# KC_BaseBoard4CompareTest-V0_1_NT_MIRR.net
KiCad netlist of a schematic drawn in Altium Designer
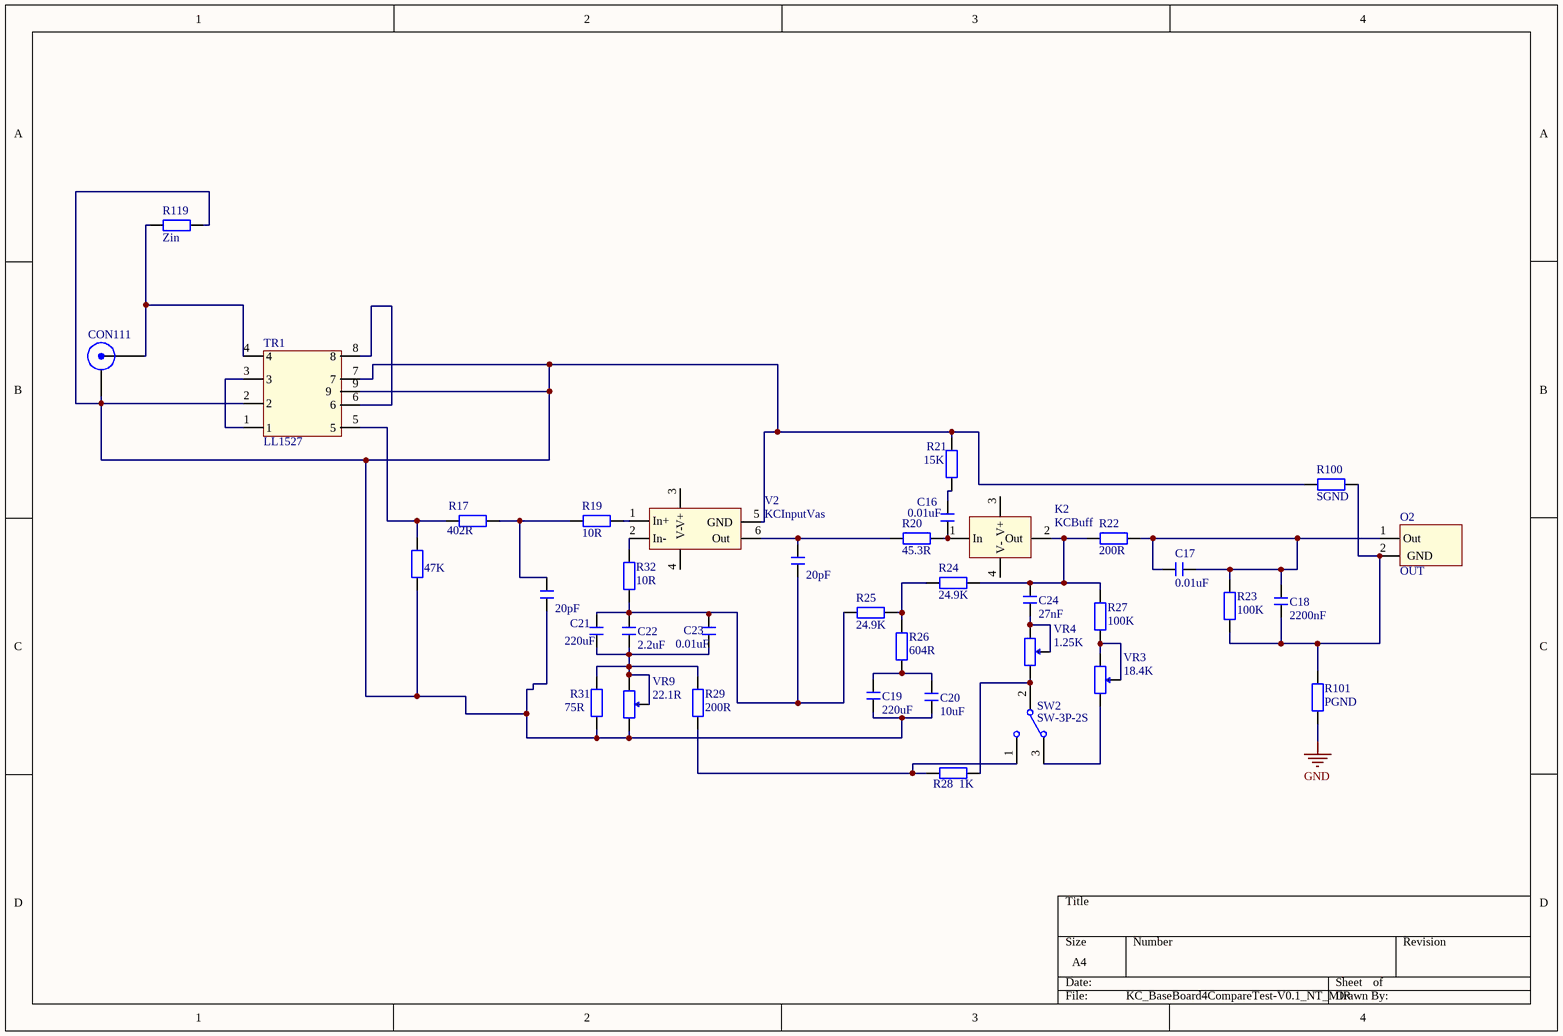
[diagram p0: KC_BaseBoard4CompareTest-V0.1_NT_MIRR.SchDoc]

(export (version "E")
  (design (tool "Eeschema 10.0.6"))
  (components
    (comp (ref "C16")
      (value "0.01uF")
      (footprint "CBB 6.3*6.3*5")
      (description "CBB电容")
      (fields (field (name "版权归属") "源创客"))
      (libsource (lib "电阻-电容-电感") (part "C-CBB"))
    )
    (comp (ref "C17")
      (value "0.01uF")
      (footprint "CBB 6.3*6.3*5")
      (description "CBB电容")
      (fields (field (name "版权归属") "源创客"))
      (libsource (lib "电阻-电容-电感") (part "C-CBB"))
    )
    (comp (ref "C18")
      (value "2200nF")
      (footprint "CBB 6.3*6.3*5")
      (description "CBB电容")
      (fields (field (name "版权归属") "源创客"))
      (libsource (lib "电阻-电容-电感") (part "C-CBB"))
    )
    (comp (ref "C19")
      (value "220uF")
      (footprint "CAP 5.0*12.5*20")
      (description "CBB电容")
      (fields (field (name "版权归属") "源创客"))
      (libsource (lib "电阻-电容-电感") (part "C-CBB"))
    )
    (comp (ref "C20")
      (value "10uF")
      (footprint "CBB 6.3*6.3*5")
      (description "CBB电容")
      (fields (field (name "版权归属") "源创客"))
      (libsource (lib "电阻-电容-电感") (part "C-CBB"))
    )
    (comp (ref "C21")
      (value "220uF")
      (footprint "CAP 5.0*12.5*20")
      (description "CBB电容")
      (fields (field (name "版权归属") "源创客"))
      (libsource (lib "电阻-电容-电感") (part "C-CBB"))
    )
    (comp (ref "C22")
      (value "2.2uF")
      (footprint "CBB 6.3*6.3*5")
      (description "CBB电容")
      (fields (field (name "版权归属") "源创客"))
      (libsource (lib "电阻-电容-电感") (part "C-CBB"))
    )
    (comp (ref "C23")
      (value "0.01uF")
      (footprint "CBB 6.3*6.3*5")
      (description "CBB电容")
      (fields (field (name "版权归属") "源创客"))
      (libsource (lib "电阻-电容-电感") (part "C-CBB"))
    )
    (comp (ref "C24")
      (value "27nF")
      (footprint "CBB 6.3*6.3*5")
      (description "CBB电容")
      (fields (field (name "版权归属") "源创客"))
      (libsource (lib "电阻-电容-电感") (part "C-CBB"))
    )
    (comp (ref "C303")
      (value "20pF")
      (footprint "CBB 6.3*6.3*5")
      (description "CBB电容")
      (fields (field (name "版权归属") "源创客"))
      (libsource (lib "电阻-电容-电感") (part "C-CBB"))
    )
    (comp (ref "C403")
      (value "20pF")
      (footprint "CBB 6.3*6.3*5")
      (description "CBB电容")
      (fields (field (name "版权归属") "源创客"))
      (libsource (lib "电阻-电容-电感") (part "C-CBB"))
    )
    (comp (ref "CON111")
      (value "RCA")
      (footprint "RCA-Wire")
      (description "RCA Connector")
      (fields (field (name "PUBLISHER") "Altium Limited"))
      (libsource (lib "Connectors") (part "RCA"))
    )
    (comp (ref "K2")
      (value "KCBuff")
      (footprint "KCBuff_M4")
      (description "King Cello Buffer Stage")
      (libsource (lib "KC_amp") (part "KCBuff"))
    )
    (comp (ref "O2")
      (value "OUT")
      (footprint "Signal_Terminal")
      (description "Signal Out")
      (libsource (lib "KC_amp") (part "Signal_Out"))
    )
    (comp (ref "R17")
      (value "402R")
      (footprint "RS 1/4W")
      (description "直插色环电阻")
      (fields (field (name "版权归属") "源创客"))
      (libsource (lib "电阻-电容-电感") (part "R-CRR"))
    )
    (comp (ref "R19")
      (value "10R")
      (footprint "RS 1/4W")
      (description "直插色环电阻")
      (fields (field (name "版权归属") "源创客"))
      (libsource (lib "电阻-电容-电感") (part "R-CRR"))
    )
    (comp (ref "R20")
      (value "45.3R")
      (footprint "RS 1/4W")
      (description "直插色环电阻")
      (fields (field (name "版权归属") "源创客"))
      (libsource (lib "电阻-电容-电感") (part "R-CRR"))
    )
    (comp (ref "R21")
      (value "15K")
      (footprint "RS 1/4W")
      (description "直插色环电阻")
      (fields (field (name "版权归属") "源创客"))
      (libsource (lib "电阻-电容-电感") (part "R-CRR"))
    )
    (comp (ref "R22")
      (value "200R")
      (footprint "RS 1/4W")
      (description "直插色环电阻")
      (fields (field (name "版权归属") "源创客"))
      (libsource (lib "电阻-电容-电感") (part "R-CRR"))
    )
    (comp (ref "R23")
      (value "100K")
      (footprint "RS 1/4W")
      (description "直插色环电阻")
      (fields (field (name "版权归属") "源创客"))
      (libsource (lib "电阻-电容-电感") (part "R-CRR"))
    )
    (comp (ref "R24")
      (value "24.9K")
      (footprint "RS 1/4W")
      (description "直插色环电阻")
      (fields (field (name "版权归属") "源创客"))
      (libsource (lib "电阻-电容-电感") (part "R-CRR"))
    )
    (comp (ref "R25")
      (value "24.9K")
      (footprint "RS 1/4W")
      (description "直插色环电阻")
      (fields (field (name "版权归属") "源创客"))
      (libsource (lib "电阻-电容-电感") (part "R-CRR"))
    )
    (comp (ref "R26")
      (value "604R")
      (footprint "RS 1/4W")
      (description "直插色环电阻")
      (fields (field (name "版权归属") "源创客"))
      (libsource (lib "电阻-电容-电感") (part "R-CRR"))
    )
    (comp (ref "R27")
      (value "100K")
      (footprint "RS 1/4W")
      (description "直插色环电阻")
      (fields (field (name "版权归属") "源创客"))
      (libsource (lib "电阻-电容-电感") (part "R-CRR"))
    )
    (comp (ref "R28")
      (value "1K")
      (footprint "RS 1/4W")
      (description "直插色环电阻")
      (fields (field (name "版权归属") "源创客"))
      (libsource (lib "电阻-电容-电感") (part "R-CRR"))
    )
    (comp (ref "R29")
      (value "200R")
      (footprint "RS 1/4W")
      (description "直插色环电阻")
      (fields (field (name "版权归属") "源创客"))
      (libsource (lib "电阻-电容-电感") (part "R-CRR"))
    )
    (comp (ref "R31")
      (value "75R")
      (footprint "RS 1/4W")
      (description "直插色环电阻")
      (fields (field (name "版权归属") "源创客"))
      (libsource (lib "电阻-电容-电感") (part "R-CRR"))
    )
    (comp (ref "R32")
      (value "10R")
      (footprint "RS 1/4W")
      (description "直插色环电阻")
      (fields (field (name "版权归属") "源创客"))
      (libsource (lib "电阻-电容-电感") (part "R-CRR"))
    )
    (comp (ref "R100")
      (value "SGND")
      (footprint "RS 1/4W")
      (description "直插色环电阻")
      (fields (field (name "版权归属") "源创客"))
      (libsource (lib "电阻-电容-电感") (part "R-CRR"))
    )
    (comp (ref "R101")
      (value "PGND")
      (footprint "RS 1/4W")
      (description "直插色环电阻")
      (fields (field (name "版权归属") "源创客"))
      (libsource (lib "电阻-电容-电感") (part "R-CRR"))
    )
    (comp (ref "R119")
      (value "Zin")
      (footprint "RS 1/4W")
      (description "直插色环电阻")
      (fields (field (name "版权归属") "源创客"))
      (libsource (lib "电阻-电容-电感") (part "R-CRR"))
    )
    (comp (ref "R183")
      (value "47K")
      (footprint "RS 1/4W")
      (description "直插色环电阻")
      (fields (field (name "版权归属") "源创客"))
      (libsource (lib "电阻-电容-电感") (part "R-CRR"))
    )
    (comp (ref "SW2")
      (value "SW-3P-2S")
      (footprint "SS-12D06")
      (description "3 Pin 2 Switch")
      (libsource (lib "Connectors") (part "SW-3P-2S"))
    )
    (comp (ref "TR1")
      (value "LL1527")
      (footprint "LL1527")
      (description "Lundahl LL1527")
      (libsource (lib "KC_amp") (part "LL1527"))
    )
    (comp (ref "V2")
      (value "KCInputVas")
      (footprint "KCIn_VAS_M4")
      (description "King Cello Input Stage and VAS")
      (libsource (lib "KC_amp") (part "KCInputVas"))
    )
    (comp (ref "VR3")
      (value "18.4K")
      (footprint "RS 1/2W-VR")
      (description "直插可调电阻-顶调")
      (libsource (lib "电阻-电容-电感") (part "VR-W"))
    )
    (comp (ref "VR4")
      (value "1.25K")
      (footprint "RS 1/2W-VR")
      (description "直插可调电阻-顶调")
      (libsource (lib "电阻-电容-电感") (part "VR-W"))
    )
    (comp (ref "VR9")
      (value "22.1R")
      (footprint "RS 1/2W-VR")
      (description "直插可调电阻-顶调")
      (libsource (lib "电阻-电容-电感") (part "VR-W"))
    )
  )
  (nets
    (net (code "1") (name "GND") (class "Default")
      (node (ref "R101") (pin "1") (pinfunction "1_1") (pintype "passive"))
    )
    (net (code "2") (name "Net-(C16-Pad2)") (class "Default")
      (node (ref "C16") (pin "2") (pinfunction "2_2") (pintype "passive"))
      (node (ref "R21") (pin "1") (pinfunction "1_1") (pintype "passive"))
    )
    (net (code "3") (name "Net-(C19-Pad1)") (class "Default")
      (node (ref "C19") (pin "1") (pinfunction "1_1") (pintype "passive"))
      (node (ref "C20") (pin "1") (pinfunction "1_1") (pintype "passive"))
      (node (ref "R26") (pin "1") (pinfunction "1_1") (pintype "passive"))
    )
    (net (code "4") (name "Net-(C21-Pad1)") (class "Default")
      (node (ref "C21") (pin "1") (pinfunction "1_1") (pintype "passive"))
      (node (ref "C22") (pin "1") (pinfunction "1_1") (pintype "passive"))
      (node (ref "C23") (pin "1") (pinfunction "1_1") (pintype "passive"))
      (node (ref "C403") (pin "1") (pinfunction "1_1") (pintype "passive"))
      (node (ref "R25") (pin "1") (pinfunction "1_1") (pintype "passive"))
      (node (ref "R32") (pin "1") (pinfunction "1_1") (pintype "passive"))
    )
    (net (code "5") (name "Net-(C21-Pad2)") (class "Default")
      (node (ref "C21") (pin "2") (pinfunction "2_2") (pintype "passive"))
      (node (ref "C22") (pin "2") (pinfunction "2_2") (pintype "passive"))
      (node (ref "C23") (pin "2") (pinfunction "2_2") (pintype "passive"))
      (node (ref "R29") (pin "2") (pinfunction "2_2") (pintype "passive"))
      (node (ref "R31") (pin "2") (pinfunction "2_2") (pintype "passive"))
      (node (ref "VR9") (pin "1") (pinfunction "1_1") (pintype "passive"))
      (node (ref "VR9") (pin "3") (pinfunction "3_3") (pintype "passive"))
    )
    (net (code "6") (name "Net-(C24-Pad2)") (class "Default")
      (node (ref "C24") (pin "2") (pinfunction "2_2") (pintype "passive"))
      (node (ref "VR4") (pin "1") (pinfunction "1_1") (pintype "passive"))
      (node (ref "VR4") (pin "3") (pinfunction "3_3") (pintype "passive"))
    )
    (net (code "7") (name "Net-(C303-Pad2)") (class "Default")
      (node (ref "C303") (pin "2") (pinfunction "2_2") (pintype "passive"))
      (node (ref "R17") (pin "2") (pinfunction "2_2") (pintype "passive"))
      (node (ref "R19") (pin "1") (pinfunction "1_1") (pintype "passive"))
    )
    (net (code "8") (name "Net-(CON111-X)") (class "Default")
      (node (ref "CON111") (pin "1") (pinfunction "X_1") (pintype "passive"))
      (node (ref "R119") (pin "1") (pinfunction "1_1") (pintype "passive"))
      (node (ref "TR1") (pin "4") (pinfunction "4_4") (pintype "passive"))
    )
    (net (code "9") (name "Net-(CON111-Y)") (class "Default")
      (node (ref "C19") (pin "2") (pinfunction "2_2") (pintype "passive"))
      (node (ref "C20") (pin "2") (pinfunction "2_2") (pintype "passive"))
      (node (ref "C303") (pin "1") (pinfunction "1_1") (pintype "passive"))
      (node (ref "CON111") (pin "2") (pinfunction "Y_2") (pintype "passive"))
      (node (ref "R100") (pin "1") (pinfunction "1_1") (pintype "passive"))
      (node (ref "R119") (pin "2") (pinfunction "2_2") (pintype "passive"))
      (node (ref "R183") (pin "1") (pinfunction "1_1") (pintype "passive"))
      (node (ref "R21") (pin "2") (pinfunction "2_2") (pintype "passive"))
      (node (ref "R31") (pin "1") (pinfunction "1_1") (pintype "passive"))
      (node (ref "TR1") (pin "2") (pinfunction "2_2") (pintype "passive"))
      (node (ref "TR1") (pin "7") (pinfunction "7_7") (pintype "passive"))
      (node (ref "TR1") (pin "9") (pinfunction "9_9") (pintype "passive"))
      (node (ref "V2") (pin "5") (pinfunction "GND_5") (pintype "passive"))
      (node (ref "VR9") (pin "2") (pinfunction "2_2") (pintype "passive"))
    )
    (net (code "10") (name "Net-(K2-In)") (class "Default")
      (node (ref "C16") (pin "1") (pinfunction "1_1") (pintype "passive"))
      (node (ref "K2") (pin "1") (pinfunction "In_1") (pintype "passive"))
      (node (ref "R20") (pin "2") (pinfunction "2_2") (pintype "passive"))
    )
    (net (code "11") (name "Net-(K2-Out)") (class "Default")
      (node (ref "C24") (pin "1") (pinfunction "1_1") (pintype "passive"))
      (node (ref "K2") (pin "2") (pinfunction "Out_2") (pintype "passive"))
      (node (ref "R22") (pin "2") (pinfunction "2_2") (pintype "passive"))
      (node (ref "R24") (pin "2") (pinfunction "2_2") (pintype "passive"))
      (node (ref "R27") (pin "1") (pinfunction "1_1") (pintype "passive"))
    )
    (net (code "12") (name "Net-(O2-GND)") (class "Default")
      (node (ref "C18") (pin "2") (pinfunction "2_2") (pintype "passive"))
      (node (ref "O2") (pin "2") (pinfunction "GND_2") (pintype "passive"))
      (node (ref "R100") (pin "2") (pinfunction "2_2") (pintype "passive"))
      (node (ref "R101") (pin "2") (pinfunction "2_2") (pintype "passive"))
      (node (ref "R23") (pin "2") (pinfunction "2_2") (pintype "passive"))
    )
    (net (code "13") (name "Net-(O2-Out)") (class "Default")
      (node (ref "C17") (pin "1") (pinfunction "1_1") (pintype "passive"))
      (node (ref "C17") (pin "2") (pinfunction "2_2") (pintype "passive"))
      (node (ref "C18") (pin "1") (pinfunction "1_1") (pintype "passive"))
      (node (ref "O2") (pin "1") (pinfunction "Out_1") (pintype "passive"))
      (node (ref "R22") (pin "1") (pinfunction "1_1") (pintype "passive"))
      (node (ref "R23") (pin "1") (pinfunction "1_1") (pintype "passive"))
    )
    (net (code "14") (name "Net-(R17-Pad1)") (class "Default")
      (node (ref "R17") (pin "1") (pinfunction "1_1") (pintype "passive"))
      (node (ref "R183") (pin "2") (pinfunction "2_2") (pintype "passive"))
      (node (ref "TR1") (pin "5") (pinfunction "5_5") (pintype "passive"))
    )
    (net (code "15") (name "Net-(R24-Pad1)") (class "Default")
      (node (ref "R24") (pin "1") (pinfunction "1_1") (pintype "passive"))
      (node (ref "R25") (pin "2") (pinfunction "2_2") (pintype "passive"))
      (node (ref "R26") (pin "2") (pinfunction "2_2") (pintype "passive"))
    )
    (net (code "16") (name "Net-(R27-Pad2)") (class "Default")
      (node (ref "R27") (pin "2") (pinfunction "2_2") (pintype "passive"))
      (node (ref "VR3") (pin "1") (pinfunction "1_1") (pintype "passive"))
      (node (ref "VR3") (pin "3") (pinfunction "3_3") (pintype "passive"))
    )
    (net (code "17") (name "Net-(R28-Pad1)") (class "Default")
      (node (ref "R28") (pin "1") (pinfunction "1_1") (pintype "passive"))
      (node (ref "R29") (pin "1") (pinfunction "1_1") (pintype "passive"))
      (node (ref "SW2") (pin "1") (pinfunction "1_1") (pintype "passive"))
    )
    (net (code "18") (name "Net-(R28-Pad2)") (class "Default")
      (node (ref "R28") (pin "2") (pinfunction "2_2") (pintype "passive"))
      (node (ref "SW2") (pin "2") (pinfunction "2_2") (pintype "passive"))
      (node (ref "VR4") (pin "2") (pinfunction "2_2") (pintype "passive"))
    )
    (net (code "19") (name "Net-(SW2-Pad3)") (class "Default")
      (node (ref "SW2") (pin "3") (pinfunction "3_3") (pintype "passive"))
      (node (ref "VR3") (pin "2") (pinfunction "2_2") (pintype "passive"))
    )
    (net (code "20") (name "Net-(TR1-Pad1)") (class "Default")
      (node (ref "TR1") (pin "1") (pinfunction "1_1") (pintype "passive"))
      (node (ref "TR1") (pin "3") (pinfunction "3_3") (pintype "passive"))
    )
    (net (code "21") (name "Net-(TR1-Pad6)") (class "Default")
      (node (ref "TR1") (pin "6") (pinfunction "6_6") (pintype "passive"))
      (node (ref "TR1") (pin "8") (pinfunction "8_8") (pintype "passive"))
    )
    (net (code "22") (name "Net-(V2-In+)") (class "Default")
      (node (ref "R19") (pin "2") (pinfunction "2_2") (pintype "passive"))
      (node (ref "V2") (pin "1") (pinfunction "In+_1") (pintype "passive"))
    )
    (net (code "23") (name "Net-(V2-In-)") (class "Default")
      (node (ref "R32") (pin "2") (pinfunction "2_2") (pintype "passive"))
      (node (ref "V2") (pin "2") (pinfunction "In-_2") (pintype "passive"))
    )
    (net (code "24") (name "Net-(V2-Out)") (class "Default")
      (node (ref "C403") (pin "2") (pinfunction "2_2") (pintype "passive"))
      (node (ref "R20") (pin "1") (pinfunction "1_1") (pintype "passive"))
      (node (ref "V2") (pin "6") (pinfunction "Out_6") (pintype "passive"))
    )
    (net (code "25") (name "unconnected-(K2-V+-Pad3)") (class "Default")
      (node (ref "K2") (pin "3") (pinfunction "V+_3") (pintype "passive"))
    )
    (net (code "26") (name "unconnected-(K2-V--Pad4)") (class "Default")
      (node (ref "K2") (pin "4") (pinfunction "V-_4") (pintype "passive"))
    )
    (net (code "27") (name "unconnected-(V2-V+-Pad3)") (class "Default")
      (node (ref "V2") (pin "3") (pinfunction "V+_3") (pintype "passive"))
    )
    (net (code "28") (name "unconnected-(V2-V--Pad4)") (class "Default")
      (node (ref "V2") (pin "4") (pinfunction "V-_4") (pintype "passive"))
    )
  )
)
